# CON_JTAG_UART.net
KiCad netlist of a schematic drawn in Altium Designer
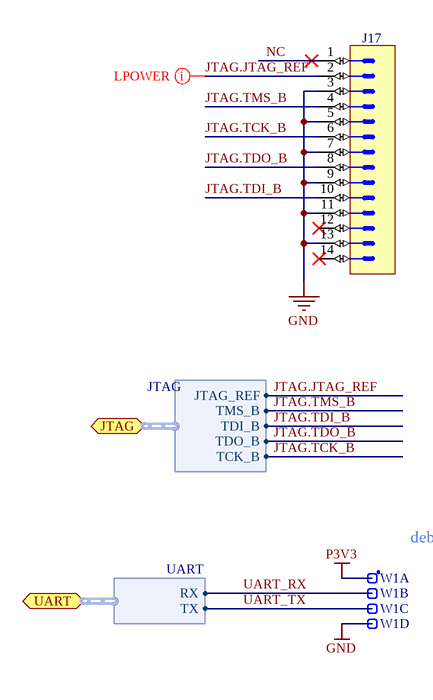
[diagram p0: CON_JTAG_UART.SchDoc]

(export (version "E")
  (design (tool "Eeschema 10.0.6"))
  (components
    (comp (ref "J17")
      (value "Milli-Grid™")
      (footprint "MOLEX_87832-1420")
      (description "Connector 14 Male")
      (fields
        (field (name "PART NUMBER") "MOLEX_87832-1420")
        (field (name "MANUFACTURER") "MOLEX")
        (field (name "AUTHOR") "CERN DEM JLC")
      )
      (libsource (lib "Connectors") (part "Connector 14 Male"))
    )
    (comp (ref "W1")
      (value "Header 4")
      (footprint "SAMTEC_HTSW-104-23-L-S")
      (description "4 Mini Wire-Wrap Contact Strip Header")
      (fields
        (field (name "PART NUMBER") "SAMTEC_HTSW-104-23-L-S")
        (field (name "MANUFACTURER") "SAMTEC")
        (field (name "AUTHOR") "CERN DEM JLC")
      )
      (libsource (lib "Connectors") (part "Wire-Wrap Contact x4"))
    )
  )
  (nets
    (net (code "3") (name "/JTAG.JTAG_REF") (class "Default")
      (node (ref "J17") (pin "2") (pinfunction "2_2") (pintype "bidirectional"))
    )
    (net (code "4") (name "/JTAG.TCK_B") (class "Default")
      (node (ref "J17") (pin "6") (pinfunction "6_6") (pintype "bidirectional"))
    )
    (net (code "5") (name "/JTAG.TDI_B") (class "Default")
      (node (ref "J17") (pin "10") (pinfunction "10_10") (pintype "bidirectional"))
    )
    (net (code "6") (name "/JTAG.TDO_B") (class "Default")
      (node (ref "J17") (pin "8") (pinfunction "8_8") (pintype "bidirectional"))
    )
    (net (code "7") (name "/JTAG.TMS_B") (class "Default")
      (node (ref "J17") (pin "4") (pinfunction "4_4") (pintype "bidirectional"))
    )
    (net (code "8") (name "/NC") (class "Default")
      (node (ref "J17") (pin "1") (pinfunction "1_1") (pintype "bidirectional"))
    )
    (net (code "9") (name "/UART_RX") (class "Default")
      (node (ref "W1") (pin "2") (pinfunction "2_2") (pintype "bidirectional"))
    )
    (net (code "10") (name "/UART_TX") (class "Default")
      (node (ref "W1") (pin "3") (pinfunction "3_3") (pintype "bidirectional"))
    )
    (net (code "13") (name "GND") (class "Default")
      (node (ref "J17") (pin "11") (pinfunction "11_11") (pintype "bidirectional"))
      (node (ref "J17") (pin "13") (pinfunction "13_13") (pintype "bidirectional"))
      (node (ref "J17") (pin "3") (pinfunction "3_3") (pintype "bidirectional"))
      (node (ref "J17") (pin "5") (pinfunction "5_5") (pintype "bidirectional"))
      (node (ref "J17") (pin "7") (pinfunction "7_7") (pintype "bidirectional"))
      (node (ref "J17") (pin "9") (pinfunction "9_9") (pintype "bidirectional"))
      (node (ref "W1") (pin "4") (pinfunction "4_4") (pintype "bidirectional"))
    )
    (net (code "14") (name "P3V3") (class "Default")
      (node (ref "W1") (pin "1") (pinfunction "1_1") (pintype "bidirectional"))
    )
    (net (code "15") (name "unconnected-(J17-Pad12)") (class "Default")
      (node (ref "J17") (pin "12") (pinfunction "12_12") (pintype "bidirectional+no_connect"))
    )
    (net (code "16") (name "unconnected-(J17-Pad14)") (class "Default")
      (node (ref "J17") (pin "14") (pinfunction "14_14") (pintype "bidirectional+no_connect"))
    )
  )
)
